# lps_regulator_rev_11.net
KiCad netlist of a schematic drawn in Altium Designer
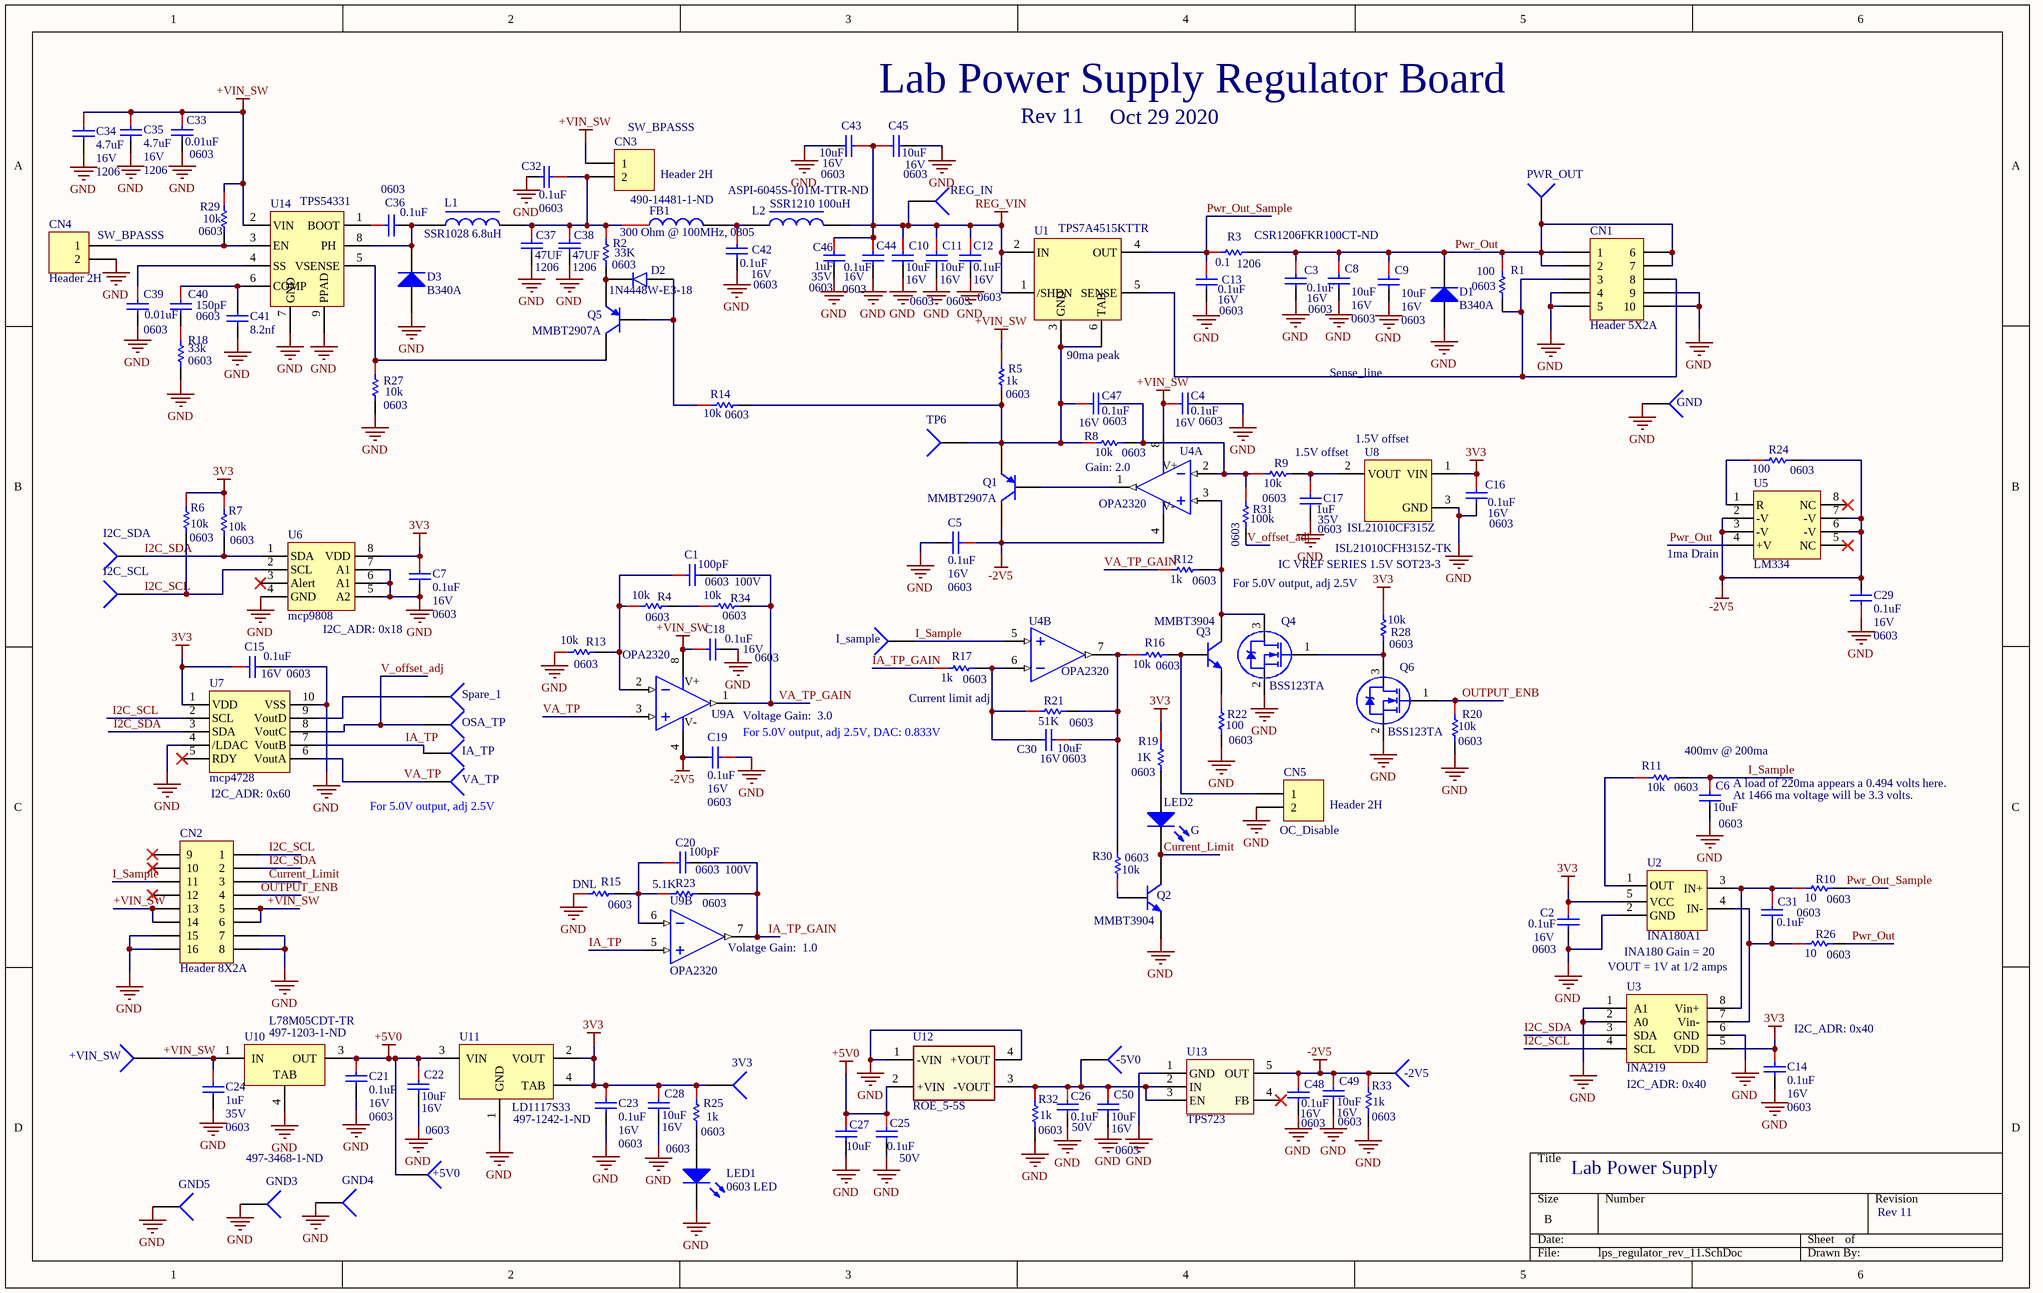
[diagram p0: lps_regulator_rev_11.SchDoc]

(export (version "E")
  (design (tool "Eeschema 10.0.6"))
  (components
    (comp (ref "+5V0")
      (value "TestPoint_BLK")
      (footprint "TestPoint-TH 42 mil")
      (description "Test Point - Black")
      (fields
        (field (name "MANUFACTURER PART NUMBER") "5001")
        (field (name "MANUFACTURER") "Keystone Electronics")
      )
      (libsource (lib "OLogic Nexus Vault") (part "TestPoint_BLK"))
    )
    (comp (ref "+VIN_SW")
      (value "TestPoint_BLK")
      (footprint "TestPoint-TH 42 mil")
      (description "Test Point - Black")
      (fields
        (field (name "MANUFACTURER PART NUMBER") "5001")
        (field (name "MANUFACTURER") "Keystone Electronics")
      )
      (libsource (lib "OLogic Nexus Vault") (part "TestPoint_BLK"))
    )
    (comp (ref "-2V5")
      (value "TestPoint_BLK")
      (footprint "TestPoint-TH 42 mil")
      (description "Test Point - Black")
      (fields
        (field (name "MANUFACTURER PART NUMBER") "5001")
        (field (name "MANUFACTURER") "Keystone Electronics")
      )
      (libsource (lib "OLogic Nexus Vault") (part "TestPoint_BLK"))
    )
    (comp (ref "-5V0")
      (value "TestPoint_BLK")
      (footprint "TestPoint-TH 42 mil")
      (description "Test Point - Black")
      (fields
        (field (name "MANUFACTURER PART NUMBER") "5001")
        (field (name "MANUFACTURER") "Keystone Electronics")
      )
      (libsource (lib "OLogic Nexus Vault") (part "TestPoint_BLK"))
    )
    (comp (ref "3V3")
      (value "TestPoint_BLK")
      (footprint "TestPoint-TH 42 mil")
      (description "Test Point - Black")
      (fields
        (field (name "MANUFACTURER PART NUMBER") "5001")
        (field (name "MANUFACTURER") "Keystone Electronics")
      )
      (libsource (lib "OLogic Nexus Vault") (part "TestPoint_BLK"))
    )
    (comp (ref "C1")
      (value "100pF")
      (footprint "CAPC0603(1608)_N")
      (description "CAP CER 100PF 50V 5% NP0 0603")
      (fields
        (field (name "VOLTAGE (RATED)") "100V")
        (field (name "PACKAGE (IMPERIAL)") "0603")
        (field (name "TOLERANCE") "5%")
      )
      (libsource (lib "OLogic Nexus Vault") (part "=Capacitance"))
    )
    (comp (ref "C2")
      (value "0.1uF")
      (footprint "CAPC0603(1608)_M")
      (description "CAP CER 0.1UF 16V 10% X7R 0603")
      (fields
        (field (name "VOLTAGE (RATED)") "16V")
        (field (name "PACKAGE (IMPERIAL)") "0603")
        (field (name "TOLERANCE") "10%")
      )
      (libsource (lib "OLogic Nexus Vault") (part "=Capacitance"))
    )
    (comp (ref "C3")
      (value "0.1uF")
      (footprint "CAPC0603(1608)_N")
      (description "CAP CER 0.1UF 16V 10% X7R 0603")
      (fields
        (field (name "VOLTAGE (RATED)") "16V")
        (field (name "PACKAGE (IMPERIAL)") "0603")
        (field (name "TOLERANCE") "10%")
      )
      (libsource (lib "OLogic Nexus Vault") (part "=Capacitance"))
    )
    (comp (ref "C4")
      (value "0.1uF")
      (footprint "CAPC0603(1608)_N")
      (description "CAP CER 0.1UF 16V 10% X7R 0603")
      (fields
        (field (name "VOLTAGE (RATED)") "16V")
        (field (name "PACKAGE (IMPERIAL)") "0603")
        (field (name "TOLERANCE") "10%")
      )
      (libsource (lib "OLogic Nexus Vault") (part "=Capacitance"))
    )
    (comp (ref "C5")
      (value "0.1uF")
      (footprint "CAPC0603(1608)_N")
      (description "CAP CER 0.1UF 16V 10% X7R 0603")
      (fields
        (field (name "VOLTAGE (RATED)") "16V")
        (field (name "PACKAGE (IMPERIAL)") "0603")
        (field (name "TOLERANCE") "10%")
      )
      (libsource (lib "OLogic Nexus Vault") (part "=Capacitance"))
    )
    (comp (ref "C6")
      (value "10uF")
      (footprint "CAPC0603(1608)_N")
      (description "CAP CER 10UF 16V X5R 0603")
      (fields (field (name "PACKAGE (IMPERIAL)") "0603") (field (name "TOLERANCE") "10%"))
      (libsource (lib "OLogic Nexus Vault") (part "=Capacitance"))
    )
    (comp (ref "C7")
      (value "0.1uF")
      (footprint "CAPC0603(1608)_M")
      (description "CAP CER 0.1UF 16V 10% X7R 0603")
      (fields
        (field (name "VOLTAGE (RATED)") "16V")
        (field (name "PACKAGE (IMPERIAL)") "0603")
        (field (name "TOLERANCE") "10%")
      )
      (libsource (lib "OLogic Nexus Vault") (part "=Capacitance"))
    )
    (comp (ref "C8")
      (value "10uF")
      (footprint "CAPC0603(1608)_N")
      (description "CAP CER 10UF 16V X5R 0603")
      (fields
        (field (name "VOLTAGE (RATED)") "16V")
        (field (name "PACKAGE (IMPERIAL)") "0603")
        (field (name "TOLERANCE") "10%")
      )
      (libsource (lib "OLogic Nexus Vault") (part "=Capacitance"))
    )
    (comp (ref "C9")
      (value "10uF")
      (footprint "CAPC0603(1608)_N")
      (description "CAP CER 10UF 16V X5R 0603")
      (fields
        (field (name "VOLTAGE (RATED)") "16V")
        (field (name "PACKAGE (IMPERIAL)") "0603")
        (field (name "TOLERANCE") "10%")
      )
      (libsource (lib "OLogic Nexus Vault") (part "=Capacitance"))
    )
    (comp (ref "C10")
      (value "10uF")
      (footprint "CAPC0603(1608)_N")
      (description "CAP CER 10UF 16V X5R 0603")
      (fields
        (field (name "VOLTAGE (RATED)") "16V")
        (field (name "PACKAGE (IMPERIAL)") "0603")
        (field (name "TOLERANCE") "10%")
      )
      (libsource (lib "OLogic Nexus Vault") (part "=Capacitance"))
    )
    (comp (ref "C11")
      (value "10uF")
      (footprint "CAPC0603(1608)_N")
      (description "CAP CER 10UF 16V X5R 0603")
      (fields
        (field (name "VOLTAGE (RATED)") "16V")
        (field (name "PACKAGE (IMPERIAL)") "0603")
        (field (name "TOLERANCE") "10%")
      )
      (libsource (lib "OLogic Nexus Vault") (part "=Capacitance"))
    )
    (comp (ref "C12")
      (value "0.1uF")
      (footprint "CAPC0603(1608)_N")
      (description "CAP CER 0.1UF 16V 10% X7R 0603")
      (fields
        (field (name "VOLTAGE (RATED)") "16V")
        (field (name "PACKAGE (IMPERIAL)") "0603")
        (field (name "TOLERANCE") "10%")
      )
      (libsource (lib "OLogic Nexus Vault") (part "=Capacitance"))
    )
    (comp (ref "C13")
      (value "0.1uF")
      (footprint "CAPC0603(1608)_M")
      (description "CAP CER 0.1UF 16V 10% X7R 0603")
      (fields
        (field (name "VOLTAGE (RATED)") "16V")
        (field (name "PACKAGE (IMPERIAL)") "0603")
        (field (name "TOLERANCE") "10%")
      )
      (libsource (lib "OLogic Nexus Vault") (part "=Capacitance"))
    )
    (comp (ref "C14")
      (value "0.1uF")
      (footprint "CAPC0603(1608)_N")
      (description "CAP CER 0.1UF 16V 10% X7R 0603")
      (fields
        (field (name "VOLTAGE (RATED)") "16V")
        (field (name "PACKAGE (IMPERIAL)") "0603")
        (field (name "TOLERANCE") "10%")
      )
      (libsource (lib "OLogic Nexus Vault") (part "=Capacitance"))
    )
    (comp (ref "C15")
      (value "0.1uF")
      (footprint "CAPC0603(1608)_N")
      (description "CAP CER 0.1UF 16V 10% X7R 0603")
      (fields
        (field (name "VOLTAGE (RATED)") "16V")
        (field (name "PACKAGE (IMPERIAL)") "0603")
        (field (name "TOLERANCE") "10%")
      )
      (libsource (lib "OLogic Nexus Vault") (part "=Capacitance"))
    )
    (comp (ref "C16")
      (value "0.1uF")
      (footprint "CAPC0603(1608)_N")
      (description "CAP CER 0.1UF 16V 10% X7R 0603")
      (fields
        (field (name "VOLTAGE (RATED)") "16V")
        (field (name "PACKAGE (IMPERIAL)") "0603")
        (field (name "TOLERANCE") "10%")
      )
      (libsource (lib "OLogic Nexus Vault") (part "=Capacitance"))
    )
    (comp (ref "C17")
      (value "1uF")
      (footprint "CAPC0603(1608)_M")
      (description "CAP CER 1UF 35V 10% X5R 0603")
      (fields
        (field (name "VOLTAGE (RATED)") "35V")
        (field (name "PACKAGE (IMPERIAL)") "0603")
        (field (name "TOLERANCE") "10%")
      )
      (libsource (lib "OLogic Nexus Vault") (part "=Capacitance"))
    )
    (comp (ref "C18")
      (value "0.1uF")
      (footprint "CAPC0603(1608)_M")
      (description "CAP CER 0.1UF 16V 10% X7R 0603")
      (fields
        (field (name "VOLTAGE (RATED)") "16V")
        (field (name "PACKAGE (IMPERIAL)") "0603")
        (field (name "TOLERANCE") "10%")
      )
      (libsource (lib "OLogic Nexus Vault") (part "=Capacitance"))
    )
    (comp (ref "C19")
      (value "0.1uF")
      (footprint "CAPC0603(1608)_M")
      (description "CAP CER 0.1UF 16V 10% X7R 0603")
      (fields
        (field (name "VOLTAGE (RATED)") "16V")
        (field (name "PACKAGE (IMPERIAL)") "0603")
        (field (name "TOLERANCE") "10%")
      )
      (libsource (lib "OLogic Nexus Vault") (part "=Capacitance"))
    )
    (comp (ref "C20")
      (value "100pF")
      (footprint "CAPC0603(1608)_N")
      (description "CAP CER 100PF 50V 5% NP0 0603")
      (fields
        (field (name "VOLTAGE (RATED)") "100V")
        (field (name "PACKAGE (IMPERIAL)") "0603")
        (field (name "TOLERANCE") "5%")
      )
      (libsource (lib "OLogic Nexus Vault") (part "=Capacitance"))
    )
    (comp (ref "C21")
      (value "0.1uF")
      (footprint "CAPC0603(1608)_M")
      (description "CAP CER 0.1UF 16V 10% X7R 0603")
      (fields
        (field (name "VOLTAGE (RATED)") "16V")
        (field (name "PACKAGE (IMPERIAL)") "0603")
        (field (name "TOLERANCE") "10%")
      )
      (libsource (lib "OLogic Nexus Vault") (part "=Capacitance"))
    )
    (comp (ref "C22")
      (value "10uF")
      (footprint "CAPC0603(1608)_N")
      (description "CAP CER 10UF 16V X5R 0603")
      (fields
        (field (name "VOLTAGE (RATED)") "16V")
        (field (name "PACKAGE (IMPERIAL)") "0603")
        (field (name "TOLERANCE") "10%")
      )
      (libsource (lib "OLogic Nexus Vault") (part "=Capacitance"))
    )
    (comp (ref "C23")
      (value "0.1uF")
      (footprint "CAPC0603(1608)_M")
      (description "CAP CER 0.1UF 16V 10% X7R 0603")
      (fields
        (field (name "VOLTAGE (RATED)") "16V")
        (field (name "PACKAGE (IMPERIAL)") "0603")
        (field (name "TOLERANCE") "10%")
      )
      (libsource (lib "OLogic Nexus Vault") (part "=Capacitance"))
    )
    (comp (ref "C24")
      (value "1uF")
      (footprint "CAPC0603(1608)_M")
      (description "CAP CER 1UF 35V 10% X5R 0603")
      (fields
        (field (name "VOLTAGE (RATED)") "35V")
        (field (name "PACKAGE (IMPERIAL)") "0603")
        (field (name "TOLERANCE") "10%")
      )
      (libsource (lib "OLogic Nexus Vault") (part "=Capacitance"))
    )
    (comp (ref "C25")
      (value "0.1uF")
      (footprint "CAPC0805(2012)_N")
      (description "0.1uF 0805 50V")
      (fields
        (field (name "MANUFACTURER") "Kemet")
        (field (name "MANUFACTURER PART NUMBER") "C0805C104K5RACTU")
        (field (name "VOLTAGE - RATED") "50V")
      )
      (libsource (lib "OLogic-Passive") (part "CAP CER 0.1UF 50V 10% X7R 0805"))
    )
    (comp (ref "C26")
      (value "0.1uF")
      (footprint "CAPC0805(2012)_N")
      (description "0.1uF 0805 50V")
      (fields
        (field (name "MANUFACTURER") "Kemet")
        (field (name "MANUFACTURER PART NUMBER") "C0805C104K5RACTU")
        (field (name "VOLTAGE - RATED") "50V")
      )
      (libsource (lib "OLogic-Passive") (part "CAP CER 0.1UF 50V 10% X7R 0805"))
    )
    (comp (ref "C27")
      (value "10uF")
      (footprint "CAPC0805(2012)_M")
      (description "10UF 0805 16V")
      (fields
        (field (name "MANUFACTURER") "Murata Electronics North America")
        (field (name "MANUFACTURER PART NUMBER") "GRM21BR61C106KE15L")
      )
      (libsource (lib "OLogic-Passive") (part "CAP CER 10UF 16V 10% X5R 0805"))
    )
    (comp (ref "C28")
      (value "10uF")
      (footprint "CAPC0603(1608)_N")
      (description "CAP CER 10UF 16V X5R 0603")
      (fields
        (field (name "VOLTAGE (RATED)") "16V")
        (field (name "PACKAGE (IMPERIAL)") "0603")
        (field (name "TOLERANCE") "10%")
      )
      (libsource (lib "OLogic Nexus Vault") (part "=Capacitance"))
    )
    (comp (ref "C29")
      (value "0.1uF")
      (footprint "CAPC0603(1608)_M")
      (description "CAP CER 0.1UF 16V 10% X7R 0603")
      (fields
        (field (name "VOLTAGE (RATED)") "16V")
        (field (name "PACKAGE (IMPERIAL)") "0603")
        (field (name "TOLERANCE") "10%")
      )
      (libsource (lib "OLogic Nexus Vault") (part "=Capacitance"))
    )
    (comp (ref "C30")
      (value "10uF")
      (footprint "CAPC0603(1608)_M")
      (description "CAP CER 0.1UF 16V 10% X7R 0603")
      (fields
        (field (name "VOLTAGE (RATED)") "16V")
        (field (name "PACKAGE (IMPERIAL)") "0603")
        (field (name "TOLERANCE") "10%")
      )
      (libsource (lib "OLogic Nexus Vault") (part "=Capacitance"))
    )
    (comp (ref "C31")
      (value "0.1uF")
      (footprint "CAPC0603(1608)_N")
      (description "CAP CER 0.1UF 16V 10% X7R 0603")
      (fields (field (name "PACKAGE (IMPERIAL)") "0603") (field (name "TOLERANCE") "10%"))
      (libsource (lib "OLogic Nexus Vault") (part "=Capacitance"))
    )
    (comp (ref "C32")
      (value "0.1uF")
      (footprint "CAPC0603(1608)_N")
      (description "CAP CER 0.1UF 16V 10% X7R 0603")
      (fields (field (name "PACKAGE (IMPERIAL)") "0603") (field (name "TOLERANCE") "10%"))
      (libsource (lib "OLogic Nexus Vault") (part "=Capacitance"))
    )
    (comp (ref "C33")
      (value "0.01uF")
      (footprint "CAPC0603(1608)_N")
      (description "CAP CER 0.01uF 50V 10% X7R 0603")
      (fields (field (name "PACKAGE (IMPERIAL)") "0603") (field (name "TOLERANCE") "10%"))
      (libsource (lib "OLogic Nexus Vault") (part "=Capacitance"))
    )
    (comp (ref "C34")
      (value "4.7uF")
      (footprint "CAPC1206(3216)_N")
      (description "CAP CER 4.7UF 50V 10% X7R 1206")
      (fields
        (field (name "VOLTAGE (RATED)") "16V")
        (field (name "PACKAGE (IMPERIAL)") "1206")
        (field (name "TOLERANCE") "10%")
      )
      (libsource (lib "OLogic Nexus Vault") (part "=Capacitance"))
    )
    (comp (ref "C35")
      (value "4.7uF")
      (footprint "CAPC1206(3216)_N")
      (description "CAP CER 4.7UF 50V 10% X7R 1206")
      (fields
        (field (name "VOLTAGE (RATED)") "16V")
        (field (name "PACKAGE (IMPERIAL)") "1206")
        (field (name "TOLERANCE") "10%")
      )
      (libsource (lib "OLogic Nexus Vault") (part "=Capacitance"))
    )
    (comp (ref "C36")
      (value "0.1uF")
      (footprint "CAPC0603(1608)_N")
      (description "CAP CER 0.1UF 16V 10% X7R 0603")
      (fields (field (name "PACKAGE (IMPERIAL)") "0603") (field (name "TOLERANCE") "10%"))
      (libsource (lib "OLogic Nexus Vault") (part "=Capacitance"))
    )
    (comp (ref "C37")
      (value "47UF")
      (footprint "CAPC1206(3216)_L")
      (description "CAP CER 47UF 25V 1206")
      (fields (field (name "PACKAGE (IMPERIAL)") "1206") (field (name "TOLERANCE") "20%"))
      (libsource (lib "OLogic Nexus Vault") (part "=Capacitance"))
    )
    (comp (ref "C38")
      (value "47UF")
      (footprint "CAPC1206(3216)_L")
      (description "CAP CER 47UF 25V 1206")
      (fields (field (name "PACKAGE (IMPERIAL)") "1206") (field (name "TOLERANCE") "20%"))
      (libsource (lib "OLogic Nexus Vault") (part "=Capacitance"))
    )
    (comp (ref "C39")
      (value "0.01uF")
      (footprint "CAPC0603(1608)_N")
      (description "CAP CER 22PF 50V 5% NP0 0603")
      (fields (field (name "PACKAGE (IMPERIAL)") "0603") (field (name "TOLERANCE") "5%"))
      (libsource (lib "OLogic Nexus Vault") (part "=Capacitance"))
    )
    (comp (ref "C40")
      (value "150pF")
      (footprint "CAPC0603(1608)_M")
      (description "CAP CER 1UF 35V 10% X5R 0603")
      (fields (field (name "PACKAGE (IMPERIAL)") "0603") (field (name "TOLERANCE") "10%"))
      (libsource (lib "OLogic Nexus Vault") (part "=Capacitance"))
    )
    (comp (ref "C41")
      (value "8.2nf")
      (footprint "CAPC1608X87X35ML15T15")
      (description "CAP CER 820PF 50V X7R 0603")
      (fields (field (name "VOLTAGE") "50V") (field (name "TOLERANCE") "10%"))
      (libsource (lib "OLogic Nexus Vault") (part "CAP"))
    )
    (comp (ref "C42")
      (value "0.1uF")
      (footprint "CAPC0603(1608)_N")
      (description "CAP CER 0.1UF 16V 10% X7R 0603")
      (fields
        (field (name "VOLTAGE (RATED)") "16V")
        (field (name "PACKAGE (IMPERIAL)") "0603")
        (field (name "TOLERANCE") "10%")
      )
      (libsource (lib "OLogic Nexus Vault") (part "=Capacitance"))
    )
    (comp (ref "C43")
      (value "10uF")
      (footprint "CAPC0603(1608)_N")
      (description "CAP CER 10UF 16V X5R 0603")
      (fields
        (field (name "VOLTAGE (RATED)") "16V")
        (field (name "PACKAGE (IMPERIAL)") "0603")
        (field (name "TOLERANCE") "10%")
      )
      (libsource (lib "OLogic Nexus Vault") (part "=Capacitance"))
    )
    (comp (ref "C44")
      (value "0.1uF")
      (footprint "CAPC0603(1608)_N")
      (description "CAP CER 0.1UF 16V 10% X7R 0603")
      (fields
        (field (name "VOLTAGE (RATED)") "16V")
        (field (name "PACKAGE (IMPERIAL)") "0603")
        (field (name "TOLERANCE") "10%")
      )
      (libsource (lib "OLogic Nexus Vault") (part "=Capacitance"))
    )
    (comp (ref "C45")
      (value "10uF")
      (footprint "CAPC0603(1608)_N")
      (description "CAP CER 10UF 16V X5R 0603")
      (fields
        (field (name "VOLTAGE (RATED)") "16V")
        (field (name "PACKAGE (IMPERIAL)") "0603")
        (field (name "TOLERANCE") "10%")
      )
      (libsource (lib "OLogic Nexus Vault") (part "=Capacitance"))
    )
    (comp (ref "C46")
      (value "1uF")
      (footprint "CAPC0603(1608)_M")
      (description "CAP CER 1UF 35V 10% X5R 0603")
      (fields
        (field (name "VOLTAGE (RATED)") "35V")
        (field (name "PACKAGE (IMPERIAL)") "0603")
        (field (name "TOLERANCE") "10%")
      )
      (libsource (lib "OLogic Nexus Vault") (part "=Capacitance"))
    )
    (comp (ref "C47")
      (value "0.1uF")
      (footprint "CAPC0603(1608)_N")
      (description "CAP CER 0.1UF 16V 10% X7R 0603")
      (fields
        (field (name "VOLTAGE (RATED)") "16V")
        (field (name "PACKAGE (IMPERIAL)") "0603")
        (field (name "TOLERANCE") "10%")
      )
      (libsource (lib "OLogic Nexus Vault") (part "=Capacitance"))
    )
    (comp (ref "C48")
      (value "0.1uF")
      (footprint "CAPC0603(1608)_M")
      (description "CAP CER 0.1UF 16V 10% X7R 0603")
      (fields
        (field (name "VOLTAGE (RATED)") "16V")
        (field (name "PACKAGE (IMPERIAL)") "0603")
        (field (name "TOLERANCE") "10%")
      )
      (libsource (lib "OLogic Nexus Vault") (part "=Capacitance"))
    )
    (comp (ref "C49")
      (value "10uF")
      (footprint "CAPC0603(1608)_N")
      (description "CAP CER 10UF 16V X5R 0603")
      (fields
        (field (name "VOLTAGE (RATED)") "16V")
        (field (name "PACKAGE (IMPERIAL)") "0603")
        (field (name "TOLERANCE") "10%")
      )
      (libsource (lib "OLogic Nexus Vault") (part "=Capacitance"))
    )
    (comp (ref "C50")
      (value "10uF")
      (footprint "CAPC0603(1608)_N")
      (description "CAP CER 10UF 16V X5R 0603")
      (fields
        (field (name "VOLTAGE (RATED)") "16V")
        (field (name "PACKAGE (IMPERIAL)") "0603")
        (field (name "TOLERANCE") "10%")
      )
      (libsource (lib "OLogic Nexus Vault") (part "=Capacitance"))
    )
    (comp (ref "CN1")
      (value "Header 5X2A")
      (footprint "HDR2X5_CEN")
      (description "Header, 5-Pin, Dual row")
      (fields (field (name "PUBLISHER") "Altium Limited"))
      (libsource (lib "OLogic Nexus Vault") (part "Header 5X2A"))
    )
    (comp (ref "CN2")
      (value "Header 8X2A")
      (footprint "HDR2X8_CEN")
      (description "Header, 8-Pin, Dual row")
      (fields (field (name "PUBLISHER") "Altium Limited"))
      (libsource (lib "OLogic Nexus Vault") (part "Header 8X2A"))
    )
    (comp (ref "CN3")
      (value "Header 2H")
      (footprint "HDR1X2H")
      (description "Header, 2-Pin, Right Angle")
      (fields
        (field (name "MANUFACTURER PART NUMBER") "M20-9960245")
        (field (name "MANUFACTURER") "Harwin Inc.")
        (field (name "PUBLISHER") "Altium Limited")
      )
      (libsource (lib "") (part "Header 2H_1"))
    )
    (comp (ref "CN4")
      (value "Header 2H")
      (footprint "HDR1X2H")
      (description "Header, 2-Pin, Right Angle")
      (fields
        (field (name "MANUFACTURER PART NUMBER") "M20-9960245")
        (field (name "MANUFACTURER") "Harwin Inc.")
        (field (name "PUBLISHER") "Altium Limited")
      )
      (libsource (lib "OLogic Nexus Vault") (part "Header 2H"))
    )
    (comp (ref "CN5")
      (value "Header 2H")
      (footprint "HDR1X2H")
      (description "Header, 2-Pin, Right Angle")
      (fields
        (field (name "MANUFACTURER PART NUMBER") "M20-9960245")
        (field (name "MANUFACTURER") "Harwin Inc.")
        (field (name "PUBLISHER") "Altium Limited")
      )
      (libsource (lib "") (part "Header 2H_1"))
    )
    (comp (ref "D1")
      (value "B340A")
      (footprint "DO-214AC")
      (description "DIODE SCHOTTKY 60V 3A")
      (fields
        (field (name "MANUFACTURER") "Micro Commercial Co")
        (field (name "MANUFACTURER PART NUMBER") "SK36A-LTP")
      )
      (libsource (lib "OLogic Nexus Vault") (part "SK36A-LTP"))
    )
    (comp (ref "D2")
      (value "1N4448W-E3-18")
      (footprint "SOD123")
      (description "Diodes - General Purpose, Power, Switching 100 Volt 500mA 4ns")
      (libsource (lib "OLogic Nexus Vault") (part "1N4448W-E3-18"))
    )
    (comp (ref "D3")
      (value "B340A")
      (footprint "DO-214AC")
      (description "DIODE SCHOTTKY 60V 3A")
      (fields
        (field (name "MANUFACTURER") "Micro Commercial Co")
        (field (name "MANUFACTURER PART NUMBER") "SK36A-LTP")
      )
      (libsource (lib "OLogic Nexus Vault") (part "SK36A-LTP"))
    )
    (comp (ref "FB1")
      (value "300 Ohm @ 100MHz, 0805")
      (footprint "RESC0805(2012)_N")
      (description "600 Ohms @ 100MHz 1 Signal Line Ferrite Bead 0805 (2012 Metric) 2A 150mOhm")
      (fields
        (field (name "MANUFACTURER PART NUMBER") "742792040")
        (field (name "MANUFACTURER") "Wurth Electronics Inc")
        (field (name "CREATOR") "osman")
      )
      (libsource (lib "OLogic Nexus Vault") (part "OL_Ferrite"))
    )
    (comp (ref "GND")
      (value "TestPoint_BLK")
      (footprint "TestPoint-TH 42 mil")
      (description "Test Point - Black")
      (fields
        (field (name "MANUFACTURER PART NUMBER") "5001")
        (field (name "MANUFACTURER") "Keystone Electronics")
      )
      (libsource (lib "OLogic Nexus Vault") (part "TestPoint_BLK"))
    )
    (comp (ref "GND3")
      (value "TestPoint_BLK")
      (footprint "TestPoint-TH 42 mil")
      (description "Test Point - Black")
      (fields
        (field (name "MANUFACTURER PART NUMBER") "5001")
        (field (name "MANUFACTURER") "Keystone Electronics")
      )
      (libsource (lib "OLogic Nexus Vault") (part "TestPoint_BLK"))
    )
    (comp (ref "GND4")
      (value "TestPoint_BLK")
      (footprint "TestPoint-TH 42 mil")
      (description "Test Point - Black")
      (fields
        (field (name "MANUFACTURER PART NUMBER") "5001")
        (field (name "MANUFACTURER") "Keystone Electronics")
      )
      (libsource (lib "OLogic Nexus Vault") (part "TestPoint_BLK"))
    )
    (comp (ref "GND5")
      (value "TestPoint_BLK")
      (footprint "TestPoint-TH 42 mil")
      (description "Test Point - Black")
      (fields
        (field (name "MANUFACTURER PART NUMBER") "5001")
        (field (name "MANUFACTURER") "Keystone Electronics")
      )
      (libsource (lib "OLogic Nexus Vault") (part "TestPoint_BLK"))
    )
    (comp (ref "I2C_SCL")
      (value "TestPoint_BLK")
      (footprint "TestPoint-TH 42 mil")
      (description "Test Point - Black")
      (fields
        (field (name "MANUFACTURER PART NUMBER") "5001")
        (field (name "MANUFACTURER") "Keystone Electronics")
      )
      (libsource (lib "OLogic Nexus Vault") (part "TestPoint_BLK"))
    )
    (comp (ref "I2C_SDA")
      (value "TestPoint_BLK")
      (footprint "TestPoint-TH 42 mil")
      (description "Test Point - Black")
      (fields
        (field (name "MANUFACTURER PART NUMBER") "5001")
        (field (name "MANUFACTURER") "Keystone Electronics")
      )
      (libsource (lib "OLogic Nexus Vault") (part "TestPoint_BLK"))
    )
    (comp (ref "IA_TP")
      (value "TestPoint_BLK")
      (footprint "TestPoint-TH 42 mil")
      (description "Test Point - Black")
      (fields
        (field (name "MANUFACTURER PART NUMBER") "5001")
        (field (name "MANUFACTURER") "Keystone Electronics")
      )
      (libsource (lib "OLogic Nexus Vault") (part "TestPoint_BLK"))
    )
    (comp (ref "I_sample")
      (value "TestPoint_BLK")
      (footprint "TestPoint-TH 42 mil")
      (description "Test Point - Black")
      (fields
        (field (name "MANUFACTURER PART NUMBER") "5001")
        (field (name "MANUFACTURER") "Keystone Electronics")
      )
      (libsource (lib "OLogic Nexus Vault") (part "TestPoint_BLK"))
    )
    (comp (ref "L1")
      (value "SSR1028 6.8uH")
      (footprint "SRU1028")
      (description "INDUCTOR 6.8uH  SMD")
      (fields (field (name "TOLERANCE") "30%"))
      (libsource (lib "OLogic Nexus Vault") (part "SSR1028"))
    )
    (comp (ref "L2")
      (value "SSR1210 100uH")
      (footprint "SRR1210")
      (description "INDUCTOR 100uH 2.2A SMD")
      (fields (field (name "TOLERANCE") "30%"))
      (libsource (lib "OLogic Nexus Vault") (part "SSR1210"))
    )
    (comp (ref "LED1")
      (value "0603 LED")
      (footprint "SM-LED-0603")
      (description "0603 SMD LED")
      (libsource (lib "OLogic Nexus Vault") (part "LED_SINGLE_GENERIC"))
    )
    (comp (ref "LED2")
      (value "G")
      (footprint "SM-LED-0603")
      (description "0603 SMD LED")
      (libsource (lib "OLogic-Diode-Opto-LED") (part "0603 LED"))
    )
    (comp (ref "OSA_TP")
      (value "TestPoint_BLK")
      (footprint "TestPoint-TH 42 mil")
      (description "Test Point - Black")
      (fields
        (field (name "MANUFACTURER PART NUMBER") "5001")
        (field (name "MANUFACTURER") "Keystone Electronics")
      )
      (libsource (lib "OLogic Nexus Vault") (part "TestPoint_BLK"))
    )
    (comp (ref "PWR_OUT")
      (value "TestPoint_BLK")
      (footprint "TestPoint-TH 42 mil")
      (description "Test Point - Black")
      (fields
        (field (name "MANUFACTURER PART NUMBER") "5001")
        (field (name "MANUFACTURER") "Keystone Electronics")
      )
      (libsource (lib "OLogic Nexus Vault") (part "TestPoint_BLK"))
    )
    (comp (ref "Q1")
      (value "MMBT2907A")
      (footprint "SOT23")
      (description "PNP General Purpose Amplifier")
      (fields (field (name "MANUFACTURER") "Fairchild Semiconductor"))
      (libsource (lib "OLogic Nexus Vault") (part "MMBT2907A"))
    )
    (comp (ref "Q2")
      (value "MMBT3904")
      (footprint "SOT23")
      (description "NPN General Purpose Amplifier")
      (fields (field (name "MANUFACTURER") "ON Semiconductor") (field (name "MPN") "MMBT3904WT1G"))
      (libsource (lib "OLogic-Trans-Drivers") (part "MMBT3904"))
    )
    (comp (ref "Q3")
      (value "MMBT3904")
      (footprint "SOT23")
      (description "NPN General Purpose Amplifier")
      (fields (field (name "MANUFACTURER") "ON Semiconductor") (field (name "MPN") "MMBT3904WT1G"))
      (libsource (lib "OLogic-Trans-Drivers") (part "MMBT3904"))
    )
    (comp (ref "Q4")
      (value "BSS123TA")
      (footprint "SOT23-3L")
      (description "MOSFET N-CH 100V 170MA SOT23-3")
      (fields (field (name "MANUFACTURER") "Diodes Incorporated"))
      (libsource (lib "OLogic Nexus Vault") (part "BSS123TA"))
    )
    (comp (ref "Q5")
      (value "MMBT2907A")
      (footprint "SOT23")
      (description "PNP General Purpose Amplifier")
      (fields (field (name "MANUFACTURER") "Fairchild Semiconductor"))
      (libsource (lib "OLogic Nexus Vault") (part "MMBT2907A"))
    )
    (comp (ref "Q6")
      (value "BSS123TA")
      (footprint "SOT23-3L")
      (description "MOSFET N-CH 100V 170MA SOT23-3")
      (fields (field (name "MANUFACTURER") "Diodes Incorporated"))
      (libsource (lib "OLogic Nexus Vault") (part "BSS123TA"))
    )
    (comp (ref "R1")
      (value "100")
      (footprint "RESC0603(1608)_N")
      (description "RES 100 OHM 1% 1/10W 0603 2017")
      (fields
        (field (name "PACKAGE (IMPERIAL)") "0603")
        (field (name "POWER") "100mW")
        (field (name "TOLERANCE") "1%")
        (field (name "RESISTANCE") "100")
      )
      (libsource (lib "OLogic Nexus Vault") (part "=Resistance"))
    )
    (comp (ref "R2")
      (value "10K")
      (footprint "RESC0603(1608)_M")
      (description "RES 10K OHM 1/10W 1% 0603 SMD")
      (fields
        (field (name "PACKAGE (IMPERIAL)") "0603")
        (field (name "RESISTANCE") "33K")
        (field (name "POWER") "100mW")
        (field (name "TOLERANCE") "1%")
      )
      (libsource (lib "OLogic Nexus Vault") (part "=Resistance"))
    )
    (comp (ref "R3")
      (value "0.33")
      (footprint "RESC1206(3216)_N")
      (description "RES 0.33 OHM 1% 1/4W 1206")
      (fields
        (field (name "PACKAGE (IMPERIAL)") "1206")
        (field (name "RESISTANCE") "0.1")
        (field (name "POWER") "250mW")
        (field (name "TOLERANCE") "1%")
      )
      (libsource (lib "OLogic Nexus Vault") (part "=Resistance"))
    )
    (comp (ref "R4")
      (value "10k")
      (footprint "RESC0603(1608)_L")
      (description "RES 10K OHM 0.1% 1/10W 0603")
      (fields
        (field (name "PACKAGE (IMPERIAL)") "0603")
        (field (name "RESISTANCE") "10k")
        (field (name "TOLERANCE") "0.1%")
        (field (name "POWER") "100mW")
      )
      (libsource (lib "OLogic Nexus Vault") (part "=Resistance"))
    )
    (comp (ref "R5")
      (value "10K")
      (footprint "RESC0603(1608)_M")
      (description "RES 10K OHM 1/10W 1% 0603 SMD")
      (fields
        (field (name "PACKAGE (IMPERIAL)") "0603")
        (field (name "RESISTANCE") "1k")
        (field (name "POWER") "100mW")
        (field (name "TOLERANCE") "1%")
      )
      (libsource (lib "OLogic Nexus Vault") (part "=Resistance"))
    )
    (comp (ref "R6")
      (value "10K")
      (footprint "RESC0603(1608)_M")
      (description "RES 10K OHM 1/10W 1% 0603 SMD")
      (fields
        (field (name "PACKAGE (IMPERIAL)") "0603")
        (field (name "RESISTANCE") "10k")
        (field (name "POWER") "100mW")
        (field (name "TOLERANCE") "1%")
      )
      (libsource (lib "OLogic Nexus Vault") (part "=Resistance"))
    )
    (comp (ref "R7")
      (value "10K")
      (footprint "RESC0603(1608)_M")
      (description "RES 10K OHM 1/10W 1% 0603 SMD")
      (fields
        (field (name "PACKAGE (IMPERIAL)") "0603")
        (field (name "RESISTANCE") "10k")
        (field (name "POWER") "100mW")
        (field (name "TOLERANCE") "1%")
      )
      (libsource (lib "OLogic Nexus Vault") (part "=Resistance"))
    )
    (comp (ref "R8")
      (value "10K")
      (footprint "RESC0603(1608)_M")
      (description "RES 10K OHM 1/10W 1% 0603 SMD")
      (fields
        (field (name "PACKAGE (IMPERIAL)") "0603")
        (field (name "RESISTANCE") "10k")
        (field (name "POWER") "100mW")
        (field (name "TOLERANCE") "1%")
      )
      (libsource (lib "OLogic Nexus Vault") (part "=Resistance"))
    )
    (comp (ref "R9")
      (value "10K")
      (footprint "RESC0603(1608)_M")
      (description "RES 10K OHM 1/10W 1% 0603 SMD")
      (fields
        (field (name "PACKAGE (IMPERIAL)") "0603")
        (field (name "RESISTANCE") "10k")
        (field (name "POWER") "100mW")
        (field (name "TOLERANCE") "1%")
      )
      (libsource (lib "OLogic Nexus Vault") (part "=Resistance"))
    )
    (comp (ref "R10")
      (value "10K")
      (footprint "RESC0603(1608)_M")
      (description "RES 10K OHM 1/10W 1% 0603 SMD")
      (fields
        (field (name "PACKAGE (IMPERIAL)") "0603")
        (field (name "RESISTANCE") "10")
        (field (name "POWER") "100mW")
        (field (name "TOLERANCE") "1%")
      )
      (libsource (lib "OLogic Nexus Vault") (part "=Resistance"))
    )
    (comp (ref "R11")
      (value "10K")
      (footprint "RESC0603(1608)_M")
      (description "RES 10K OHM 1/10W 1% 0603 SMD")
      (fields
        (field (name "PACKAGE (IMPERIAL)") "0603")
        (field (name "RESISTANCE") "10k")
        (field (name "POWER") "100mW")
        (field (name "TOLERANCE") "1%")
      )
      (libsource (lib "OLogic Nexus Vault") (part "=Resistance"))
    )
    (comp (ref "R12")
      (value "1.0K")
      (footprint "RESC0603(1608)_M")
      (description "RES 1K OHM 1% 1/10W 0603")
      (fields
        (field (name "PACKAGE (IMPERIAL)") "0603")
        (field (name "POWER") "100mW")
        (field (name "RESISTANCE") "1k")
        (field (name "TOLERANCE") "1%")
      )
      (libsource (lib "OLogic Nexus Vault") (part "=Resistance"))
    )
    (comp (ref "R13")
      (value "10k")
      (footprint "RESC0603(1608)_L")
      (description "RES 10K OHM 0.1% 1/10W 0603")
      (fields
        (field (name "PACKAGE (IMPERIAL)") "0603")
        (field (name "RESISTANCE") "10k")
        (field (name "TOLERANCE") "0.1%")
        (field (name "POWER") "100mW")
      )
      (libsource (lib "OLogic Nexus Vault") (part "=Resistance"))
    )
    (comp (ref "R14")
      (value "10K")
      (footprint "RESC0603(1608)_M")
      (description "RES 10K OHM 1/10W 1% 0603 SMD")
      (fields
        (field (name "PACKAGE (IMPERIAL)") "0603")
        (field (name "RESISTANCE") "10k")
        (field (name "POWER") "100mW")
        (field (name "TOLERANCE") "1%")
      )
      (libsource (lib "OLogic Nexus Vault") (part "=Resistance"))
    )
    (comp (ref "R15")
      (value "1.0K")
      (footprint "RESC0603(1608)_M")
      (description "RES 1K OHM 1% 1/10W 0603")
      (fields
        (field (name "PACKAGE (IMPERIAL)") "0603")
        (field (name "POWER") "100mW")
        (field (name "RESISTANCE") "DNL")
        (field (name "TOLERANCE") "1%")
      )
      (libsource (lib "OLogic Nexus Vault") (part "=Resistance"))
    )
    (comp (ref "R16")
      (value "1.0K")
      (footprint "RESC0603(1608)_M")
      (description "RES 1K OHM 1% 1/10W 0603")
      (fields
        (field (name "PACKAGE (IMPERIAL)") "0603")
        (field (name "POWER") "100mW")
        (field (name "RESISTANCE") "10k")
        (field (name "TOLERANCE") "1%")
      )
      (libsource (lib "OLogic Nexus Vault") (part "=Resistance"))
    )
    (comp (ref "R17")
      (value "1.0K")
      (footprint "RESC0603(1608)_M")
      (description "RES 1K OHM 1% 1/10W 0603")
      (fields
        (field (name "PACKAGE (IMPERIAL)") "0603")
        (field (name "POWER") "100mW")
        (field (name "RESISTANCE") "1k")
        (field (name "TOLERANCE") "1%")
      )
      (libsource (lib "OLogic Nexus Vault") (part "=Resistance"))
    )
    (comp (ref "R18")
      (value "33K")
      (footprint "RESC0603(1608)_N")
      (description "RES 33K OHM 1/10W 5% 0603 SMD")
      (fields
        (field (name "PACKAGE (IMPERIAL)") "0603")
        (field (name "TOLERANCE") "5%")
        (field (name "POWER") "100mW")
        (field (name "RESISTANCE") "33k")
      )
      (libsource (lib "OLogic Nexus Vault") (part "=Resistance"))
    )
    (comp (ref "R19")
      (value "1.0K")
      (footprint "RESC0603(1608)_M")
      (description "RES 1K OHM 1% 1/10W 0603")
      (fields
        (field (name "PACKAGE (IMPERIAL)") "0603")
        (field (name "POWER") "100mW")
        (field (name "RESISTANCE") "1K")
        (field (name "TOLERANCE") "1%")
      )
      (libsource (lib "OLogic Nexus Vault") (part "=Resistance"))
    )
    (comp (ref "R20")
      (value "10K")
      (footprint "RESC0603(1608)_M")
      (description "RES 10K OHM 1/10W 1% 0603 SMD")
      (fields
        (field (name "PACKAGE (IMPERIAL)") "0603")
        (field (name "RESISTANCE") "10k")
        (field (name "POWER") "100mW")
        (field (name "TOLERANCE") "1%")
      )
      (libsource (lib "OLogic Nexus Vault") (part "=Resistance"))
    )
    (comp (ref "R21")
      (value "100K")
      (footprint "RESC0603(1608)_M")
      (description "RES 100K OHM 1% 1/10W 0603")
      (fields
        (field (name "PACKAGE (IMPERIAL)") "0603")
        (field (name "RESISTANCE") "51K")
        (field (name "POWER") "100mW")
        (field (name "TOLERANCE") "1%")
      )
      (libsource (lib "OLogic Nexus Vault") (part "=Resistance"))
    )
    (comp (ref "R22")
      (value "1.0K")
      (footprint "RESC0603(1608)_M")
      (description "RES 1K OHM 1% 1/10W 0603")
      (fields
        (field (name "PACKAGE (IMPERIAL)") "0603")
        (field (name "POWER") "100mW")
        (field (name "RESISTANCE") "100")
        (field (name "TOLERANCE") "1%")
      )
      (libsource (lib "OLogic Nexus Vault") (part "=Resistance"))
    )
    (comp (ref "R23")
      (value "100")
      (footprint "RESC0603(1608)_N")
      (description "RES 100 OHM 1% 1/10W 0603 2017")
      (fields
        (field (name "PACKAGE (IMPERIAL)") "0603")
        (field (name "POWER") "100mW")
        (field (name "TOLERANCE") "1%")
        (field (name "RESISTANCE") "5.1K")
      )
      (libsource (lib "OLogic Nexus Vault") (part "=Resistance"))
    )
    (comp (ref "R24")
      (value "100")
      (footprint "RESC0603(1608)_N")
      (description "RES 100 OHM 1% 1/10W 0603 2017")
      (fields
        (field (name "PACKAGE (IMPERIAL)") "0603")
        (field (name "POWER") "100mW")
        (field (name "TOLERANCE") "1%")
        (field (name "RESISTANCE") "100")
      )
      (libsource (lib "OLogic Nexus Vault") (part "=Resistance"))
    )
    (comp (ref "R25")
      (value "1.0K")
      (footprint "RESC0603(1608)_M")
      (description "RES 1K OHM 1% 1/10W 0603")
      (fields
        (field (name "PACKAGE (IMPERIAL)") "0603")
        (field (name "POWER") "100mW")
        (field (name "RESISTANCE") "1k")
        (field (name "TOLERANCE") "1%")
      )
      (libsource (lib "OLogic Nexus Vault") (part "=Resistance"))
    )
    (comp (ref "R26")
      (value "10K")
      (footprint "RESC0603(1608)_M")
      (description "RES 10K OHM 1/10W 1% 0603 SMD")
      (fields
        (field (name "PACKAGE (IMPERIAL)") "0603")
        (field (name "RESISTANCE") "10")
        (field (name "POWER") "100mW")
        (field (name "TOLERANCE") "1%")
      )
      (libsource (lib "OLogic Nexus Vault") (part "=Resistance"))
    )
    (comp (ref "R27")
      (value "10K")
      (footprint "RESC0603(1608)_M")
      (description "RES 10K OHM 1/10W 1% 0603 SMD")
      (fields
        (field (name "PACKAGE (IMPERIAL)") "0603")
        (field (name "RESISTANCE") "10k")
        (field (name "POWER") "100mW")
        (field (name "TOLERANCE") "1%")
      )
      (libsource (lib "OLogic Nexus Vault") (part "=Resistance"))
    )
    (comp (ref "R28")
      (value "10K")
      (footprint "RESC0603(1608)_M")
      (description "RES 10K OHM 1/10W 1% 0603 SMD")
      (fields
        (field (name "PACKAGE (IMPERIAL)") "0603")
        (field (name "RESISTANCE") "10k")
        (field (name "POWER") "100mW")
        (field (name "TOLERANCE") "1%")
      )
      (libsource (lib "OLogic Nexus Vault") (part "=Resistance"))
    )
    (comp (ref "R29")
      (value "10K")
      (footprint "RESC0603(1608)_M")
      (description "RES 10K OHM 1/10W 1% 0603 SMD")
      (fields
        (field (name "PACKAGE (IMPERIAL)") "0603")
        (field (name "RESISTANCE") "10k")
        (field (name "POWER") "100mW")
        (field (name "TOLERANCE") "1%")
      )
      (libsource (lib "OLogic Nexus Vault") (part "=Resistance"))
    )
    (comp (ref "R30")
      (value "1.0K")
      (footprint "RESC0603(1608)_M")
      (description "RES 1K OHM 1% 1/10W 0603")
      (fields
        (field (name "PACKAGE (IMPERIAL)") "0603")
        (field (name "POWER") "100mW")
        (field (name "RESISTANCE") "10k")
        (field (name "TOLERANCE") "1%")
      )
      (libsource (lib "OLogic Nexus Vault") (part "=Resistance"))
    )
    (comp (ref "R31")
      (value "1.0K")
      (footprint "RESC0603(1608)_M")
      (description "RES 1K OHM 1% 1/10W 0603")
      (fields
        (field (name "PACKAGE (IMPERIAL)") "0603")
        (field (name "POWER") "100mW")
        (field (name "RESISTANCE") "100k")
        (field (name "TOLERANCE") "1%")
      )
      (libsource (lib "OLogic Nexus Vault") (part "=Resistance"))
    )
    (comp (ref "R32")
      (value "1.0K")
      (footprint "RESC0603(1608)_M")
      (description "RES 1K OHM 1% 1/10W 0603")
      (fields
        (field (name "PACKAGE (IMPERIAL)") "0603")
        (field (name "POWER") "100mW")
        (field (name "RESISTANCE") "1k")
        (field (name "TOLERANCE") "1%")
      )
      (libsource (lib "OLogic Nexus Vault") (part "=Resistance"))
    )
    (comp (ref "R33")
      (value "1.0K")
      (footprint "RESC0603(1608)_M")
      (description "RES 1K OHM 1% 1/10W 0603")
      (fields
        (field (name "PACKAGE (IMPERIAL)") "0603")
        (field (name "POWER") "100mW")
        (field (name "RESISTANCE") "1k")
        (field (name "TOLERANCE") "1%")
      )
      (libsource (lib "OLogic Nexus Vault") (part "=Resistance"))
    )
    (comp (ref "R34")
      (value "10k")
      (footprint "RESC0603(1608)_L")
      (description "RES 10K OHM 0.1% 1/10W 0603")
      (fields
        (field (name "PACKAGE (IMPERIAL)") "0603")
        (field (name "RESISTANCE") "10k")
        (field (name "TOLERANCE") "0.1%")
        (field (name "POWER") "100mW")
      )
      (libsource (lib "OLogic Nexus Vault") (part "=Resistance"))
    )
    (comp (ref "REG_IN")
      (value "TestPoint_BLK")
      (footprint "TestPoint-TH 42 mil")
      (description "Test Point - Black")
      (fields
        (field (name "MANUFACTURER PART NUMBER") "5001")
        (field (name "MANUFACTURER") "Keystone Electronics")
      )
      (libsource (lib "OLogic Nexus Vault") (part "TestPoint_BLK"))
    )
    (comp (ref "Spare_1")
      (value "TestPoint_BLK")
      (footprint "TestPoint-TH 42 mil")
      (description "Test Point - Black")
      (fields
        (field (name "MANUFACTURER PART NUMBER") "5001")
        (field (name "MANUFACTURER") "Keystone Electronics")
      )
      (libsource (lib "OLogic Nexus Vault") (part "TestPoint_BLK"))
    )
    (comp (ref "TP6")
      (value "TestPoint_BLK")
      (footprint "TestPoint-TH 42 mil")
      (description "Test Point - Black")
      (fields
        (field (name "MANUFACTURER PART NUMBER") "5001")
        (field (name "MANUFACTURER") "Keystone Electronics")
      )
      (libsource (lib "OLogic Nexus Vault") (part "TestPoint_BLK"))
    )
    (comp (ref "U1")
      (value "TPS7A4515KTTR")
      (footprint "TPS7A4515KTTR")
      (description "TPS7A4515KTTR, linear regulator")
      (libsource (lib "hdmi_lvds") (part "TPS7A4515KTTR"))
    )
    (comp (ref "U2")
      (value "INA180A1")
      (footprint "SOT-23-5_MC")
      (libsource (lib "hdmi_lvds") (part "INA180A1"))
    )
    (comp (ref "U3")
      (value "INA219")
      (footprint "INA219")
      (description "Current Monitor IC")
      (libsource (lib "hdmi_lvds") (part "INA219"))
    )
    (comp (ref "U4")
      (value "OPA2320")
      (footprint "SOIC-8_NoPad")
      (description "Dual Single Supply Rail-to-Rail OpAmp")
      (fields
        (field (name "MANUFACTURER PART NUMBER") "OPA2320AIDR")
        (field (name "BASE PART NUMBER") "OPA2320")
        (field (name "MANUFACTURER") "Texas Instruments")
      )
      (libsource (lib "OLogic Nexus Vault") (part "OPA2320"))
    )
    (comp (ref "U5")
      (value "LM334")
      (footprint "LM334")
      (description "LM334, Current source")
      (libsource (lib "hdmi_lvds") (part "LM334"))
    )
    (comp (ref "U6") (value "mcp9808") (footprint "8MSOP") (libsource (lib "hdmi_lvds") (part "mcp9808")))
    (comp (ref "U7")
      (value "mcp4728")
      (footprint "MCP4728")
      (description "MCP4728")
      (libsource (lib "hdmi_lvds") (part "mcp4728"))
    )
    (comp (ref "U8")
      (value "ISL21010CF315Z")
      (footprint "SOT23")
      (libsource (lib "hdmi_lvds") (part "ISL21010CF315Z"))
    )
    (comp (ref "U9")
      (value "OPA2320")
      (footprint "SOIC-8_NoPad")
      (description "Dual Single Supply Rail-to-Rail OpAmp")
      (fields
        (field (name "MANUFACTURER PART NUMBER") "OPA2320AIDR")
        (field (name "BASE PART NUMBER") "OPA2320")
        (field (name "MANUFACTURER") "Texas Instruments")
      )
      (libsource (lib "OLogic Nexus Vault") (part "OPA2320"))
    )
    (comp (ref "U10")
      (value "~")
      (footprint "TO-252_N")
      (libsource (lib "OLogic Nexus Vault") (part "PM-REG-LD29150-SOT3"))
    )
    (comp (ref "U11")
      (value "LD1117S33")
      (footprint "DSO-G3")
      (description "3.3 volt fixed regulator, 800mA")
      (libsource (lib "OLogic Nexus Vault") (part "LD1117S33"))
    )
    (comp (ref "U12")
      (value "ROE_5-5S")
      (footprint "ROE_5-55")
      (description "isolated DC/DC  converter")
      (libsource (lib "*") (part "ROE_5-5S"))
    )
    (comp (ref "U13") (value "TPS723") (footprint "SOt-23-5") (libsource (lib "*") (part "TPS723")))
    (comp (ref "U14")
      (value "TPS54331")
      (footprint "TPS54331")
      (libsource (lib "hdmi_lvds") (part "TPS54331"))
    )
    (comp (ref "VA_TP")
      (value "TestPoint_BLK")
      (footprint "TestPoint-TH 42 mil")
      (description "Test Point - Black")
      (fields
        (field (name "MANUFACTURER PART NUMBER") "5001")
        (field (name "MANUFACTURER") "Keystone Electronics")
      )
      (libsource (lib "OLogic Nexus Vault") (part "TestPoint_BLK"))
    )
  )
  (nets
    (net (code "1") (name "+5V0") (class "Default")
      (node (ref "+5V0") (pin "1") (pinfunction "1_1") (pintype "passive"))
      (node (ref "C21") (pin "1") (pinfunction "1_1") (pintype "passive"))
      (node (ref "C22") (pin "1") (pinfunction "1_1") (pintype "passive"))
      (node (ref "C25") (pin "1") (pinfunction "1_1") (pintype "passive"))
      (node (ref "C27") (pin "1") (pinfunction "1_1") (pintype "passive"))
      (node (ref "U10") (pin "3") (pinfunction "OUT_3") (pintype "power_in"))
      (node (ref "U11") (pin "3") (pinfunction "VIN_3") (pintype "power_in"))
      (node (ref "U12") (pin "2") (pinfunction "+VIN_2") (pintype "power_in"))
    )
    (net (code "2") (name "+VIN_SW") (class "Default")
      (node (ref "+VIN_SW") (pin "1") (pinfunction "1_1") (pintype "passive"))
      (node (ref "C18") (pin "1") (pinfunction "1_1") (pintype "passive"))
      (node (ref "C24") (pin "1") (pinfunction "1_1") (pintype "passive"))
      (node (ref "C33") (pin "1") (pinfunction "1_1") (pintype "passive"))
      (node (ref "C34") (pin "1") (pinfunction "1_1") (pintype "passive"))
      (node (ref "C35") (pin "1") (pinfunction "1_1") (pintype "passive"))
      (node (ref "C4") (pin "1") (pinfunction "1_1") (pintype "passive"))
      (node (ref "CN2") (pin "13") (pinfunction "13_13") (pintype "passive"))
      (node (ref "CN2") (pin "14") (pinfunction "14_14") (pintype "passive"))
      (node (ref "CN2") (pin "5") (pinfunction "5_5") (pintype "passive"))
      (node (ref "CN2") (pin "6") (pinfunction "6_6") (pintype "passive"))
      (node (ref "CN3") (pin "1") (pinfunction "1_1") (pintype "passive"))
      (node (ref "R29") (pin "1") (pinfunction "1_1") (pintype "passive"))
      (node (ref "R5") (pin "1") (pinfunction "1_1") (pintype "passive"))
      (node (ref "U10") (pin "1") (pinfunction "IN_1") (pintype "power_in"))
      (node (ref "U14") (pin "2") (pinfunction "VIN_2") (pintype "passive"))
      (node (ref "U4") (pin "8") (pinfunction "V+_8") (pintype "power_in"))
      (node (ref "U9") (pin "8") (pinfunction "V+_8") (pintype "power_in"))
    )
    (net (code "3") (name "-2V5") (class "Default")
      (node (ref "-2V5") (pin "1") (pinfunction "1_1") (pintype "passive"))
      (node (ref "C19") (pin "2") (pinfunction "2_2") (pintype "passive"))
      (node (ref "C29") (pin "2") (pinfunction "2_2") (pintype "passive"))
      (node (ref "C48") (pin "1") (pinfunction "1_1") (pintype "passive"))
      (node (ref "C49") (pin "1") (pinfunction "1_1") (pintype "passive"))
      (node (ref "C5") (pin "1") (pinfunction "1_1") (pintype "passive"))
      (node (ref "Q1") (pin "3") (pinfunction "C_3") (pintype "passive"))
      (node (ref "R24") (pin "2") (pinfunction "2_2") (pintype "passive"))
      (node (ref "R33") (pin "1") (pinfunction "1_1") (pintype "passive"))
      (node (ref "U13") (pin "5") (pinfunction "OUT_5") (pintype "passive"))
      (node (ref "U4") (pin "4") (pinfunction "V-_4") (pintype "power_in"))
      (node (ref "U5") (pin "2") (pinfunction "-V_2") (pintype "passive"))
      (node (ref "U5") (pin "3") (pinfunction "-V_3") (pintype "passive"))
      (node (ref "U5") (pin "6") (pinfunction "-V_6") (pintype "passive"))
      (node (ref "U5") (pin "7") (pinfunction "-V_7") (pintype "passive"))
      (node (ref "U9") (pin "4") (pinfunction "V-_4") (pintype "power_in"))
    )
    (net (code "4") (name "/Current_Limit") (class "Default")
      (node (ref "CN2") (pin "3") (pinfunction "3_3") (pintype "passive"))
      (node (ref "LED2") (pin "2") (pinfunction "2_2") (pintype "passive"))
      (node (ref "Q2") (pin "3") (pinfunction "C_3") (pintype "passive"))
    )
    (net (code "5") (name "/I2C_SCL") (class "Default")
      (node (ref "CN2") (pin "1") (pinfunction "1_1") (pintype "passive"))
      (node (ref "I2C_SCL") (pin "1") (pinfunction "1_1") (pintype "passive"))
      (node (ref "R6") (pin "2") (pinfunction "2_2") (pintype "passive"))
      (node (ref "U3") (pin "4") (pinfunction "SCL_4") (pintype "passive"))
      (node (ref "U6") (pin "2") (pinfunction "SCL_2") (pintype "passive"))
      (node (ref "U7") (pin "2") (pinfunction "SCL_2") (pintype "passive"))
    )
    (net (code "6") (name "/I2C_SDA") (class "Default")
      (node (ref "CN2") (pin "2") (pinfunction "2_2") (pintype "passive"))
      (node (ref "I2C_SDA") (pin "1") (pinfunction "1_1") (pintype "passive"))
      (node (ref "R7") (pin "2") (pinfunction "2_2") (pintype "passive"))
      (node (ref "U3") (pin "3") (pinfunction "SDA_3") (pintype "passive"))
      (node (ref "U6") (pin "1") (pinfunction "SDA_1") (pintype "passive"))
      (node (ref "U7") (pin "3") (pinfunction "SDA_3") (pintype "passive"))
    )
    (net (code "7") (name "/IA_TP") (class "Default")
      (node (ref "IA_TP") (pin "1") (pinfunction "1_1") (pintype "passive"))
      (node (ref "U7") (pin "7") (pinfunction "VoutB_7") (pintype "passive"))
      (node (ref "U9") (pin "5") (pinfunction "INB+_5") (pintype "input"))
    )
    (net (code "8") (name "/IA_TP_GAIN") (class "Default")
      (node (ref "C20") (pin "2") (pinfunction "2_2") (pintype "passive"))
      (node (ref "R17") (pin "1") (pinfunction "1_1") (pintype "passive"))
      (node (ref "R23") (pin "2") (pinfunction "2_2") (pintype "passive"))
      (node (ref "U9") (pin "7") (pinfunction "OUTB_7") (pintype "output"))
    )
    (net (code "9") (name "/I_Sample") (class "Default")
      (node (ref "C6") (pin "1") (pinfunction "1_1") (pintype "passive"))
      (node (ref "CN2") (pin "11") (pinfunction "11_11") (pintype "passive"))
      (node (ref "I_sample") (pin "1") (pinfunction "1_1") (pintype "passive"))
      (node (ref "R11") (pin "2") (pinfunction "2_2") (pintype "passive"))
      (node (ref "U4") (pin "5") (pinfunction "INB+_5") (pintype "input"))
    )
    (net (code "10") (name "/OUTPUT_ENB") (class "Default")
      (node (ref "CN2") (pin "4") (pinfunction "4_4") (pintype "passive"))
      (node (ref "Q6") (pin "1") (pinfunction "G_1") (pintype "passive"))
      (node (ref "R20") (pin "1") (pinfunction "1_1") (pintype "passive"))
    )
    (net (code "11") (name "/Pwr_Out") (class "Default")
      (node (ref "C3") (pin "1") (pinfunction "1_1") (pintype "passive"))
      (node (ref "C8") (pin "1") (pinfunction "1_1") (pintype "passive"))
      (node (ref "C9") (pin "1") (pinfunction "1_1") (pintype "passive"))
      (node (ref "CN1") (pin "1") (pinfunction "1_1") (pintype "passive"))
      (node (ref "CN1") (pin "2") (pinfunction "2_2") (pintype "passive"))
      (node (ref "CN1") (pin "6") (pinfunction "6_6") (pintype "passive"))
      (node (ref "CN1") (pin "7") (pinfunction "7_7") (pintype "passive"))
      (node (ref "D1") (pin "2") (pinfunction "K_2") (pintype "passive"))
      (node (ref "PWR_OUT") (pin "1") (pinfunction "1_1") (pintype "passive"))
      (node (ref "R1") (pin "1") (pinfunction "1_1") (pintype "passive"))
      (node (ref "R26") (pin "2") (pinfunction "2_2") (pintype "passive"))
      (node (ref "R3") (pin "2") (pinfunction "2_2") (pintype "passive"))
      (node (ref "U5") (pin "4") (pinfunction "+V_4") (pintype "passive"))
    )
    (net (code "12") (name "/Pwr_Out_Sample") (class "Default")
      (node (ref "C13") (pin "1") (pinfunction "1_1") (pintype "passive"))
      (node (ref "R10") (pin "2") (pinfunction "2_2") (pintype "passive"))
      (node (ref "R3") (pin "1") (pinfunction "1_1") (pintype "passive"))
      (node (ref "U1") (pin "4") (pinfunction "OUT_4") (pintype "passive"))
    )
    (net (code "13") (name "/VA_TP") (class "Default")
      (node (ref "U7") (pin "6") (pinfunction "VoutA_6") (pintype "passive"))
      (node (ref "U9") (pin "3") (pinfunction "INA+_3") (pintype "input"))
      (node (ref "VA_TP") (pin "1") (pinfunction "1_1") (pintype "passive"))
    )
    (net (code "14") (name "/VA_TP_GAIN") (class "Default")
      (node (ref "C1") (pin "2") (pinfunction "2_2") (pintype "passive"))
      (node (ref "R12") (pin "1") (pinfunction "1_1") (pintype "passive"))
      (node (ref "R34") (pin "2") (pinfunction "2_2") (pintype "passive"))
      (node (ref "U9") (pin "1") (pinfunction "OUTA_1") (pintype "output"))
    )
    (net (code "15") (name "/V_offset_adj") (class "Default")
      (node (ref "OSA_TP") (pin "1") (pinfunction "1_1") (pintype "passive"))
      (node (ref "R31") (pin "2") (pinfunction "2_2") (pintype "passive"))
      (node (ref "U7") (pin "8") (pinfunction "VoutC_8") (pintype "passive"))
    )
    (net (code "16") (name "3V3") (class "Default")
      (node (ref "3V3") (pin "1") (pinfunction "1_1") (pintype "passive"))
      (node (ref "C14") (pin "1") (pinfunction "1_1") (pintype "passive"))
      (node (ref "C15") (pin "1") (pinfunction "1_1") (pintype "passive"))
      (node (ref "C16") (pin "1") (pinfunction "1_1") (pintype "passive"))
      (node (ref "C2") (pin "1") (pinfunction "1_1") (pintype "passive"))
      (node (ref "C23") (pin "1") (pinfunction "1_1") (pintype "passive"))
      (node (ref "C28") (pin "1") (pinfunction "1_1") (pintype "passive"))
      (node (ref "C7") (pin "1") (pinfunction "1_1") (pintype "passive"))
      (node (ref "R19") (pin "1") (pinfunction "1_1") (pintype "passive"))
      (node (ref "R25") (pin "1") (pinfunction "1_1") (pintype "passive"))
      (node (ref "R28") (pin "1") (pinfunction "1_1") (pintype "passive"))
      (node (ref "R6") (pin "1") (pinfunction "1_1") (pintype "passive"))
      (node (ref "R7") (pin "1") (pinfunction "1_1") (pintype "passive"))
      (node (ref "U11") (pin "2") (pinfunction "VOUT_2") (pintype "power_in"))
      (node (ref "U11") (pin "4") (pinfunction "TAB_4") (pintype "power_in"))
      (node (ref "U2") (pin "5") (pinfunction "VCC_5") (pintype "passive"))
      (node (ref "U3") (pin "5") (pinfunction "VDD_5") (pintype "passive"))
      (node (ref "U6") (pin "8") (pinfunction "VDD_8") (pintype "passive"))
      (node (ref "U7") (pin "1") (pinfunction "VDD_1") (pintype "passive"))
      (node (ref "U8") (pin "1") (pinfunction "VIN_1") (pintype "passive"))
    )
    (net (code "17") (name "GND") (class "Default")
      (node (ref "C10") (pin "2") (pinfunction "2_2") (pintype "passive"))
      (node (ref "C11") (pin "2") (pinfunction "2_2") (pintype "passive"))
      (node (ref "C12") (pin "2") (pinfunction "2_2") (pintype "passive"))
      (node (ref "C13") (pin "2") (pinfunction "2_2") (pintype "passive"))
      (node (ref "C14") (pin "2") (pinfunction "2_2") (pintype "passive"))
      (node (ref "C15") (pin "2") (pinfunction "2_2") (pintype "passive"))
      (node (ref "C16") (pin "2") (pinfunction "2_2") (pintype "passive"))
      (node (ref "C17") (pin "2") (pinfunction "2_2") (pintype "passive"))
      (node (ref "C18") (pin "2") (pinfunction "2_2") (pintype "passive"))
      (node (ref "C19") (pin "1") (pinfunction "1_1") (pintype "passive"))
      (node (ref "C2") (pin "2") (pinfunction "2_2") (pintype "passive"))
      (node (ref "C21") (pin "2") (pinfunction "2_2") (pintype "passive"))
      (node (ref "C22") (pin "2") (pinfunction "2_2") (pintype "passive"))
      (node (ref "C23") (pin "2") (pinfunction "2_2") (pintype "passive"))
      (node (ref "C24") (pin "2") (pinfunction "2_2") (pintype "passive"))
      (node (ref "C25") (pin "2") (pinfunction "2_2") (pintype "passive"))
      (node (ref "C26") (pin "2") (pinfunction "2_2") (pintype "passive"))
      (node (ref "C27") (pin "2") (pinfunction "2_2") (pintype "passive"))
      (node (ref "C28") (pin "2") (pinfunction "2_2") (pintype "passive"))
      (node (ref "C29") (pin "1") (pinfunction "1_1") (pintype "passive"))
      (node (ref "C3") (pin "2") (pinfunction "2_2") (pintype "passive"))
      (node (ref "C32") (pin "2") (pinfunction "2_2") (pintype "passive"))
      (node (ref "C33") (pin "2") (pinfunction "2_2") (pintype "passive"))
      (node (ref "C34") (pin "2") (pinfunction "2_2") (pintype "passive"))
      (node (ref "C35") (pin "2") (pinfunction "2_2") (pintype "passive"))
      (node (ref "C37") (pin "2") (pinfunction "2_2") (pintype "passive"))
      (node (ref "C38") (pin "2") (pinfunction "2_2") (pintype "passive"))
      (node (ref "C39") (pin "2") (pinfunction "2_2") (pintype "passive"))
      (node (ref "C4") (pin "2") (pinfunction "2_2") (pintype "passive"))
      (node (ref "C41") (pin "1") (pinfunction "1_1") (pintype "passive"))
      (node (ref "C42") (pin "2") (pinfunction "2_2") (pintype "passive"))
      (node (ref "C43") (pin "2") (pinfunction "2_2") (pintype "passive"))
      (node (ref "C44") (pin "2") (pinfunction "2_2") (pintype "passive"))
      (node (ref "C45") (pin "2") (pinfunction "2_2") (pintype "passive"))
      (node (ref "C46") (pin "2") (pinfunction "2_2") (pintype "passive"))
      (node (ref "C48") (pin "2") (pinfunction "2_2") (pintype "passive"))
      (node (ref "C49") (pin "2") (pinfunction "2_2") (pintype "passive"))
      (node (ref "C5") (pin "2") (pinfunction "2_2") (pintype "passive"))
      (node (ref "C50") (pin "2") (pinfunction "2_2") (pintype "passive"))
      (node (ref "C6") (pin "2") (pinfunction "2_2") (pintype "passive"))
      (node (ref "C7") (pin "2") (pinfunction "2_2") (pintype "passive"))
      (node (ref "C8") (pin "2") (pinfunction "2_2") (pintype "passive"))
      (node (ref "C9") (pin "2") (pinfunction "2_2") (pintype "passive"))
      (node (ref "CN1") (pin "10") (pinfunction "10_10") (pintype "passive"))
      (node (ref "CN1") (pin "4") (pinfunction "4_4") (pintype "passive"))
      (node (ref "CN1") (pin "5") (pinfunction "5_5") (pintype "passive"))
      (node (ref "CN1") (pin "9") (pinfunction "9_9") (pintype "passive"))
      (node (ref "CN2") (pin "15") (pinfunction "15_15") (pintype "passive"))
      (node (ref "CN2") (pin "16") (pinfunction "16_16") (pintype "passive"))
      (node (ref "CN2") (pin "7") (pinfunction "7_7") (pintype "passive"))
      (node (ref "CN2") (pin "8") (pinfunction "8_8") (pintype "passive"))
      (node (ref "CN4") (pin "2") (pinfunction "2_2") (pintype "passive"))
      (node (ref "CN5") (pin "2") (pinfunction "2_2") (pintype "passive"))
      (node (ref "D1") (pin "1") (pinfunction "A_1") (pintype "passive"))
      (node (ref "D3") (pin "1") (pinfunction "A_1") (pintype "passive"))
      (node (ref "GND") (pin "1") (pinfunction "1_1") (pintype "passive"))
      (node (ref "GND3") (pin "1") (pinfunction "1_1") (pintype "passive"))
      (node (ref "GND4") (pin "1") (pinfunction "1_1") (pintype "passive"))
      (node (ref "GND5") (pin "1") (pinfunction "1_1") (pintype "passive"))
      (node (ref "LED1") (pin "2") (pinfunction "Cathode_2") (pintype "passive"))
      (node (ref "Q2") (pin "2") (pinfunction "E_2") (pintype "passive"))
      (node (ref "Q4") (pin "2") (pinfunction "S_2") (pintype "passive"))
      (node (ref "Q6") (pin "2") (pinfunction "S_2") (pintype "passive"))
      (node (ref "R13") (pin "1") (pinfunction "1_1") (pintype "passive"))
      (node (ref "R15") (pin "1") (pinfunction "1_1") (pintype "passive"))
      (node (ref "R18") (pin "2") (pinfunction "2_2") (pintype "passive"))
      (node (ref "R20") (pin "2") (pinfunction "2_2") (pintype "passive"))
      (node (ref "R22") (pin "2") (pinfunction "2_2") (pintype "passive"))
      (node (ref "R27") (pin "2") (pinfunction "2_2") (pintype "passive"))
      (node (ref "R32") (pin "2") (pinfunction "2_2") (pintype "passive"))
      (node (ref "R33") (pin "2") (pinfunction "2_2") (pintype "passive"))
      (node (ref "U10") (pin "4") (pinfunction "TAB_4") (pintype "passive"))
      (node (ref "U11") (pin "1") (pinfunction "GND_1") (pintype "power_in"))
      (node (ref "U12") (pin "1") (pinfunction "-VIN_1") (pintype "power_in"))
      (node (ref "U12") (pin "4") (pinfunction "+VOUT_4") (pintype "power_in"))
      (node (ref "U13") (pin "1") (pinfunction "GND_1") (pintype "passive"))
      (node (ref "U14") (pin "7") (pinfunction "GND_7") (pintype "passive"))
      (node (ref "U14") (pin "9") (pinfunction "PPAD_9") (pintype "passive"))
      (node (ref "U2") (pin "2") (pinfunction "GND_2") (pintype "passive"))
      (node (ref "U3") (pin "1") (pinfunction "A1_1") (pintype "passive"))
      (node (ref "U3") (pin "2") (pinfunction "A0_2") (pintype "passive"))
      (node (ref "U3") (pin "6") (pinfunction "GND_6") (pintype "passive"))
      (node (ref "U6") (pin "4") (pinfunction "GND_4") (pintype "passive"))
      (node (ref "U6") (pin "5") (pinfunction "A2_5") (pintype "passive"))
      (node (ref "U6") (pin "6") (pinfunction "A1_6") (pintype "passive"))
      (node (ref "U6") (pin "7") (pinfunction "A1_7") (pintype "passive"))
      (node (ref "U7") (pin "10") (pinfunction "VSS_10") (pintype "passive"))
      (node (ref "U7") (pin "4") (pinfunction "/LDAC_4") (pintype "passive"))
      (node (ref "U8") (pin "3") (pinfunction "GND_3") (pintype "passive"))
    )
    (net (code "18") (name "Net-(C32-Pad1)") (class "Default")
      (node (ref "C32") (pin "1") (pinfunction "1_1") (pintype "passive"))
      (node (ref "C37") (pin "1") (pinfunction "1_1") (pintype "passive"))
      (node (ref "C38") (pin "1") (pinfunction "1_1") (pintype "passive"))
      (node (ref "CN3") (pin "2") (pinfunction "2_2") (pintype "passive"))
      (node (ref "FB1") (pin "1") (pinfunction "1_1") (pintype "passive"))
      (node (ref "L1") (pin "2") (pinfunction "2_2") (pintype "passive"))
      (node (ref "R2") (pin "1") (pinfunction "1_1") (pintype "passive"))
    )
    (net (code "19") (name "Net-(C40-Pad2)") (class "Default")
      (node (ref "C40") (pin "2") (pinfunction "2_2") (pintype "passive"))
      (node (ref "R18") (pin "1") (pinfunction "1_1") (pintype "passive"))
    )
    (net (code "20") (name "Net-(C42-Pad1)") (class "Default")
      (node (ref "C42") (pin "1") (pinfunction "1_1") (pintype "passive"))
      (node (ref "FB1") (pin "2") (pinfunction "2_2") (pintype "passive"))
      (node (ref "L2") (pin "1") (pinfunction "1_1") (pintype "passive"))
    )
    (net (code "21") (name "Net-(D2-A)") (class "Default")
      (node (ref "D2") (pin "1") (pinfunction "A_1") (pintype "passive"))
      (node (ref "Q5") (pin "1") (pinfunction "B_1") (pintype "passive"))
      (node (ref "R14") (pin "1") (pinfunction "1_1") (pintype "passive"))
    )
    (net (code "22") (name "Net-(D2-C)") (class "Default")
      (node (ref "D2") (pin "2") (pinfunction "C_2") (pintype "passive"))
      (node (ref "Q5") (pin "2") (pinfunction "E_2") (pintype "passive"))
      (node (ref "R2") (pin "2") (pinfunction "2_2") (pintype "passive"))
    )
    (net (code "23") (name "Net-(D3-K)") (class "Default")
      (node (ref "C36") (pin "2") (pinfunction "2_2") (pintype "passive"))
      (node (ref "D3") (pin "2") (pinfunction "K_2") (pintype "passive"))
      (node (ref "L1") (pin "1") (pinfunction "1_1") (pintype "passive"))
      (node (ref "U14") (pin "8") (pinfunction "PH_8") (pintype "passive"))
    )
    (net (code "24") (name "Net-(LED1-Anode)") (class "Default")
      (node (ref "LED1") (pin "1") (pinfunction "Anode_1") (pintype "passive"))
      (node (ref "R25") (pin "2") (pinfunction "2_2") (pintype "passive"))
    )
    (net (code "25") (name "Net-(LED2-Pad1)") (class "Default")
      (node (ref "LED2") (pin "1") (pinfunction "1_1") (pintype "passive"))
      (node (ref "R19") (pin "2") (pinfunction "2_2") (pintype "passive"))
    )
    (net (code "26") (name "Net-(Q1-B)") (class "Default")
      (node (ref "Q1") (pin "1") (pinfunction "B_1") (pintype "passive"))
      (node (ref "U4") (pin "1") (pinfunction "OUTA_1") (pintype "output"))
    )
    (net (code "27") (name "Net-(Q1-E)") (class "Default")
      (node (ref "C47") (pin "1") (pinfunction "1_1") (pintype "passive"))
      (node (ref "Q1") (pin "2") (pinfunction "E_2") (pintype "passive"))
      (node (ref "R14") (pin "2") (pinfunction "2_2") (pintype "passive"))
      (node (ref "R5") (pin "2") (pinfunction "2_2") (pintype "passive"))
      (node (ref "R8") (pin "1") (pinfunction "1_1") (pintype "passive"))
      (node (ref "TP6") (pin "1") (pinfunction "1_1") (pintype "passive"))
      (node (ref "U1") (pin "3") (pinfunction "GND_3") (pintype "passive"))
      (node (ref "U1") (pin "6") (pinfunction "TAB_6") (pintype "passive"))
    )
    (net (code "28") (name "Net-(Q2-B)") (class "Default")
      (node (ref "Q2") (pin "1") (pinfunction "B_1") (pintype "passive"))
      (node (ref "R30") (pin "1") (pinfunction "1_1") (pintype "passive"))
    )
    (net (code "29") (name "Net-(Q3-B)") (class "Default")
      (node (ref "CN5") (pin "1") (pinfunction "1_1") (pintype "passive"))
      (node (ref "Q3") (pin "1") (pinfunction "B_1") (pintype "passive"))
      (node (ref "R16") (pin "2") (pinfunction "2_2") (pintype "passive"))
    )
    (net (code "30") (name "Net-(Q3-C)") (class "Default")
      (node (ref "Q3") (pin "3") (pinfunction "C_3") (pintype "passive"))
      (node (ref "Q4") (pin "3") (pinfunction "D_3") (pintype "passive"))
      (node (ref "R12") (pin "2") (pinfunction "2_2") (pintype "passive"))
      (node (ref "U4") (pin "3") (pinfunction "INA+_3") (pintype "input"))
    )
    (net (code "31") (name "Net-(Q3-E)") (class "Default")
      (node (ref "Q3") (pin "2") (pinfunction "E_2") (pintype "passive"))
      (node (ref "R22") (pin "1") (pinfunction "1_1") (pintype "passive"))
    )
    (net (code "32") (name "Net-(Q4-G)") (class "Default")
      (node (ref "Q4") (pin "1") (pinfunction "G_1") (pintype "passive"))
      (node (ref "Q6") (pin "3") (pinfunction "D_3") (pintype "passive"))
      (node (ref "R28") (pin "2") (pinfunction "2_2") (pintype "passive"))
    )
    (net (code "33") (name "Net-(Q5-C)") (class "Default")
      (node (ref "Q5") (pin "3") (pinfunction "C_3") (pintype "passive"))
      (node (ref "R27") (pin "1") (pinfunction "1_1") (pintype "passive"))
      (node (ref "U14") (pin "5") (pinfunction "VSENSE_5") (pintype "passive"))
    )
    (net (code "34") (name "Net-(R34-Pad1)") (class "Default")
      (node (ref "R34") (pin "1") (pinfunction "1_1") (pintype "passive"))
      (node (ref "R4") (pin "2") (pinfunction "2_2") (pintype "passive"))
    )
    (net (code "35") (name "Net-(U1-SENSE)") (class "Default")
      (node (ref "CN1") (pin "3") (pinfunction "3_3") (pintype "passive"))
      (node (ref "CN1") (pin "8") (pinfunction "8_8") (pintype "passive"))
      (node (ref "R1") (pin "2") (pinfunction "2_2") (pintype "passive"))
      (node (ref "U1") (pin "5") (pinfunction "SENSE_5") (pintype "passive"))
    )
    (net (code "36") (name "Net-(U2-IN+)") (class "Default")
      (node (ref "C31") (pin "1") (pinfunction "1_1") (pintype "passive"))
      (node (ref "R10") (pin "1") (pinfunction "1_1") (pintype "passive"))
      (node (ref "U2") (pin "3") (pinfunction "IN+_3") (pintype "passive"))
      (node (ref "U3") (pin "8") (pinfunction "Vin+_8") (pintype "passive"))
    )
    (net (code "37") (name "Net-(U2-IN-)") (class "Default")
      (node (ref "C31") (pin "2") (pinfunction "2_2") (pintype "passive"))
      (node (ref "R26") (pin "1") (pinfunction "1_1") (pintype "passive"))
      (node (ref "U2") (pin "4") (pinfunction "IN-_4") (pintype "passive"))
      (node (ref "U3") (pin "7") (pinfunction "Vin-_7") (pintype "passive"))
    )
    (net (code "38") (name "Net-(U2-OUT)") (class "Default")
      (node (ref "R11") (pin "1") (pinfunction "1_1") (pintype "passive"))
      (node (ref "U2") (pin "1") (pinfunction "OUT_1") (pintype "passive"))
    )
    (net (code "39") (name "Net-(U4A-INA-)") (class "Default")
      (node (ref "C47") (pin "2") (pinfunction "2_2") (pintype "passive"))
      (node (ref "R31") (pin "1") (pinfunction "1_1") (pintype "passive"))
      (node (ref "R8") (pin "2") (pinfunction "2_2") (pintype "passive"))
      (node (ref "R9") (pin "1") (pinfunction "1_1") (pintype "passive"))
      (node (ref "U4") (pin "2") (pinfunction "INA-_2") (pintype "input"))
    )
    (net (code "40") (name "Net-(U4B-INB-)") (class "Default")
      (node (ref "C30") (pin "2") (pinfunction "2_2") (pintype "passive"))
      (node (ref "R17") (pin "2") (pinfunction "2_2") (pintype "passive"))
      (node (ref "R21") (pin "1") (pinfunction "1_1") (pintype "passive"))
      (node (ref "U4") (pin "6") (pinfunction "INB-_6") (pintype "input"))
    )
    (net (code "41") (name "Net-(U4B-OUTB)") (class "Default")
      (node (ref "C30") (pin "1") (pinfunction "1_1") (pintype "passive"))
      (node (ref "R16") (pin "1") (pinfunction "1_1") (pintype "passive"))
      (node (ref "R21") (pin "2") (pinfunction "2_2") (pintype "passive"))
      (node (ref "R30") (pin "2") (pinfunction "2_2") (pintype "passive"))
      (node (ref "U4") (pin "7") (pinfunction "OUTB_7") (pintype "output"))
    )
    (net (code "42") (name "Net-(U5-R)") (class "Default")
      (node (ref "R24") (pin "1") (pinfunction "1_1") (pintype "passive"))
      (node (ref "U5") (pin "1") (pinfunction "R_1") (pintype "passive"))
    )
    (net (code "43") (name "Net-(U7-VoutD)") (class "Default")
      (node (ref "Spare_1") (pin "1") (pinfunction "1_1") (pintype "passive"))
      (node (ref "U7") (pin "9") (pinfunction "VoutD_9") (pintype "passive"))
    )
    (net (code "44") (name "Net-(U8-VOUT)") (class "Default")
      (node (ref "C17") (pin "1") (pinfunction "1_1") (pintype "passive"))
      (node (ref "R9") (pin "2") (pinfunction "2_2") (pintype "passive"))
      (node (ref "U8") (pin "2") (pinfunction "VOUT_2") (pintype "passive"))
    )
    (net (code "45") (name "Net-(U9A-INA-)") (class "Default")
      (node (ref "C1") (pin "1") (pinfunction "1_1") (pintype "passive"))
      (node (ref "R13") (pin "2") (pinfunction "2_2") (pintype "passive"))
      (node (ref "R4") (pin "1") (pinfunction "1_1") (pintype "passive"))
      (node (ref "U9") (pin "2") (pinfunction "INA-_2") (pintype "input"))
    )
    (net (code "46") (name "Net-(U9B-INB-)") (class "Default")
      (node (ref "C20") (pin "1") (pinfunction "1_1") (pintype "passive"))
      (node (ref "R15") (pin "2") (pinfunction "2_2") (pintype "passive"))
      (node (ref "R23") (pin "1") (pinfunction "1_1") (pintype "passive"))
      (node (ref "U9") (pin "6") (pinfunction "INB-_6") (pintype "input"))
    )
    (net (code "47") (name "Net-(U12--VOUT)") (class "Default")
      (node (ref "-5V0") (pin "1") (pinfunction "1_1") (pintype "passive"))
      (node (ref "C26") (pin "1") (pinfunction "1_1") (pintype "passive"))
      (node (ref "C50") (pin "1") (pinfunction "1_1") (pintype "passive"))
      (node (ref "R32") (pin "1") (pinfunction "1_1") (pintype "passive"))
      (node (ref "U12") (pin "3") (pinfunction "-VOUT_3") (pintype "passive"))
      (node (ref "U13") (pin "2") (pinfunction "IN_2") (pintype "passive"))
      (node (ref "U13") (pin "3") (pinfunction "EN_3") (pintype "passive"))
    )
    (net (code "48") (name "Net-(U14-BOOT)") (class "Default")
      (node (ref "C36") (pin "1") (pinfunction "1_1") (pintype "passive"))
      (node (ref "U14") (pin "1") (pinfunction "BOOT_1") (pintype "passive"))
    )
    (net (code "49") (name "Net-(U14-COMP)") (class "Default")
      (node (ref "C40") (pin "1") (pinfunction "1_1") (pintype "passive"))
      (node (ref "C41") (pin "2") (pinfunction "2_2") (pintype "passive"))
      (node (ref "U14") (pin "6") (pinfunction "COMP_6") (pintype "passive"))
    )
    (net (code "50") (name "Net-(U14-EN)") (class "Default")
      (node (ref "CN4") (pin "1") (pinfunction "1_1") (pintype "passive"))
      (node (ref "R29") (pin "2") (pinfunction "2_2") (pintype "passive"))
      (node (ref "U14") (pin "3") (pinfunction "EN_3") (pintype "passive"))
    )
    (net (code "51") (name "Net-(U14-SS)") (class "Default")
      (node (ref "C39") (pin "1") (pinfunction "1_1") (pintype "passive"))
      (node (ref "U14") (pin "4") (pinfunction "SS_4") (pintype "passive"))
    )
    (net (code "52") (name "REG_VIN") (class "Default")
      (node (ref "C10") (pin "1") (pinfunction "1_1") (pintype "passive"))
      (node (ref "C11") (pin "1") (pinfunction "1_1") (pintype "passive"))
      (node (ref "C12") (pin "1") (pinfunction "1_1") (pintype "passive"))
      (node (ref "C43") (pin "1") (pinfunction "1_1") (pintype "passive"))
      (node (ref "C44") (pin "1") (pinfunction "1_1") (pintype "passive"))
      (node (ref "C45") (pin "1") (pinfunction "1_1") (pintype "passive"))
      (node (ref "C46") (pin "1") (pinfunction "1_1") (pintype "passive"))
      (node (ref "L2") (pin "2") (pinfunction "2_2") (pintype "passive"))
      (node (ref "REG_IN") (pin "1") (pinfunction "1_1") (pintype "passive"))
      (node (ref "U1") (pin "1") (pinfunction "/SHDN_1") (pintype "passive"))
      (node (ref "U1") (pin "2") (pinfunction "IN_2") (pintype "passive"))
    )
    (net (code "53") (name "unconnected-(CN2-Pad9)") (class "Default")
      (node (ref "CN2") (pin "9") (pinfunction "9_9") (pintype "passive+no_connect"))
    )
    (net (code "54") (name "unconnected-(CN2-Pad10)") (class "Default")
      (node (ref "CN2") (pin "10") (pinfunction "10_10") (pintype "passive+no_connect"))
    )
    (net (code "55") (name "unconnected-(CN2-Pad12)") (class "Default")
      (node (ref "CN2") (pin "12") (pinfunction "12_12") (pintype "passive+no_connect"))
    )
    (net (code "56") (name "unconnected-(U5-NC-Pad5)") (class "Default")
      (node (ref "U5") (pin "5") (pinfunction "NC_5") (pintype "passive+no_connect"))
    )
    (net (code "57") (name "unconnected-(U5-NC-Pad8)") (class "Default")
      (node (ref "U5") (pin "8") (pinfunction "NC_8") (pintype "passive+no_connect"))
    )
    (net (code "58") (name "unconnected-(U6-Alert-Pad3)") (class "Default")
      (node (ref "U6") (pin "3") (pinfunction "Alert_3") (pintype "passive+no_connect"))
    )
    (net (code "59") (name "unconnected-(U7-RDY-Pad5)") (class "Default")
      (node (ref "U7") (pin "5") (pinfunction "RDY_5") (pintype "passive+no_connect"))
    )
    (net (code "60") (name "unconnected-(U13-FB-Pad4)") (class "Default")
      (node (ref "U13") (pin "4") (pinfunction "FB_4") (pintype "passive+no_connect"))
    )
  )
)
